# USB_TYPE_C.net
KiCad netlist of a schematic drawn in Altium Designer
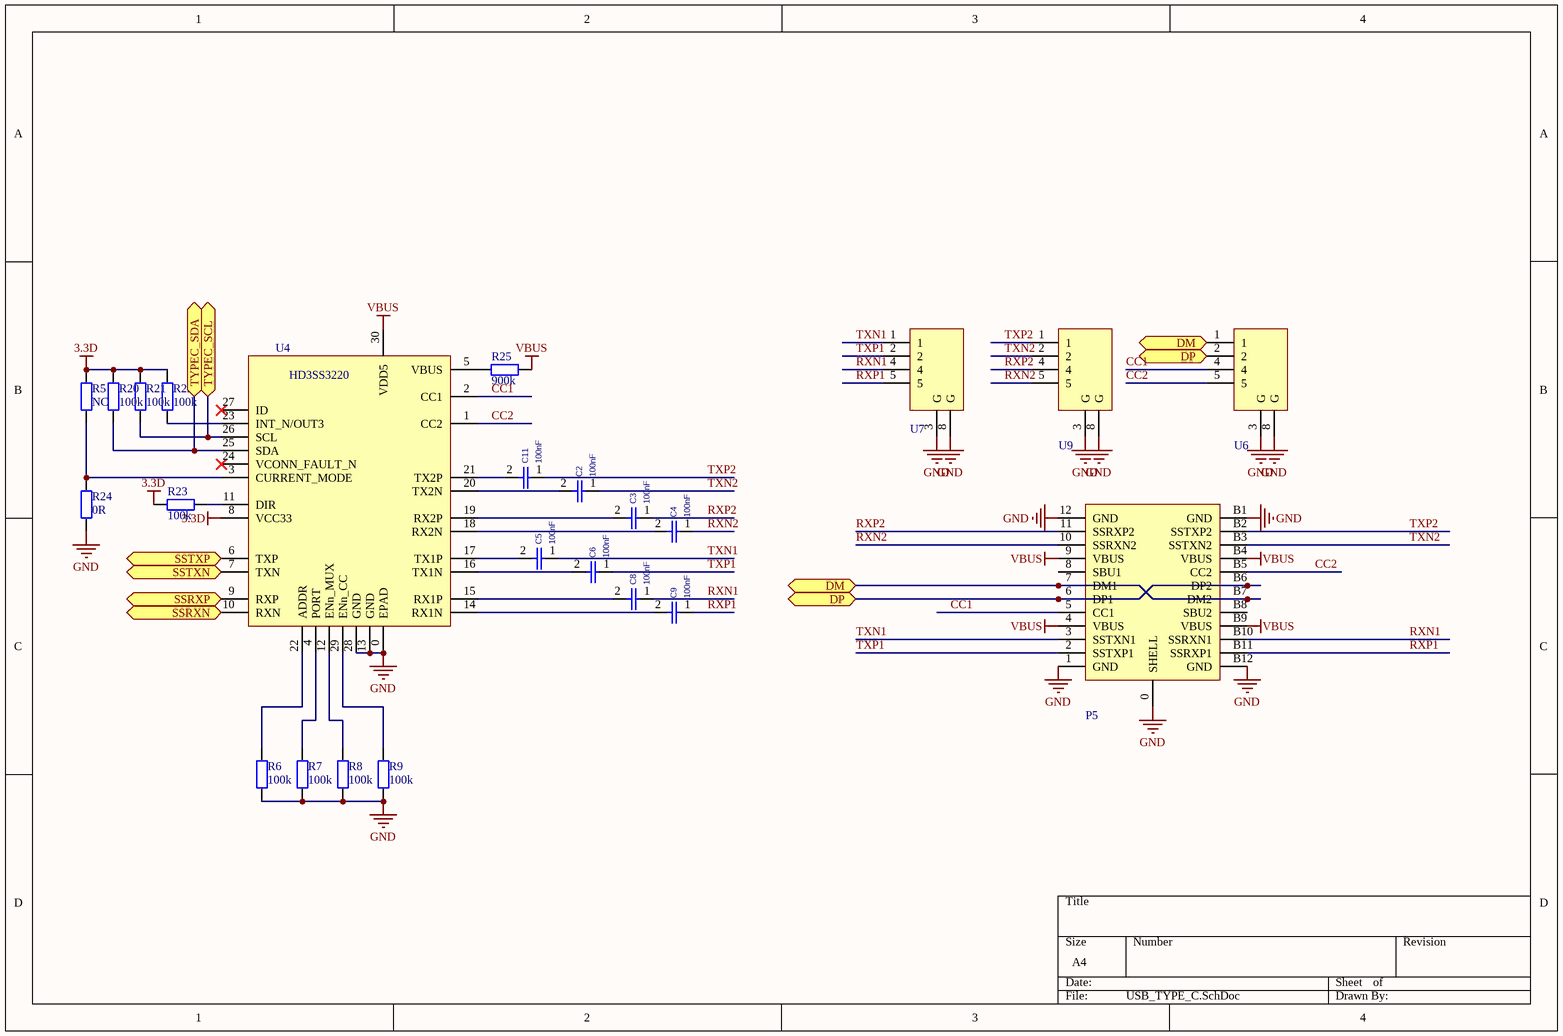
[diagram p0: USB_TYPE_C.SchDoc]

(export (version "E")
  (design (tool "Eeschema 10.0.6"))
  (components
    (comp (ref "C2") (value "100nF") (footprint "0201") (libsource (lib "*") (part "CAP/0402")))
    (comp (ref "C3") (value "100nF") (footprint "0201") (libsource (lib "*") (part "CAP/0402")))
    (comp (ref "C4") (value "100nF") (footprint "0201") (libsource (lib "*") (part "CAP/0402")))
    (comp (ref "C5") (value "100nF") (footprint "0201") (libsource (lib "*") (part "CAP/0402")))
    (comp (ref "C6") (value "100nF") (footprint "0201") (libsource (lib "*") (part "CAP/0402")))
    (comp (ref "C8") (value "100nF") (footprint "0201") (libsource (lib "*") (part "CAP/0402")))
    (comp (ref "C9") (value "100nF") (footprint "0201") (libsource (lib "*") (part "CAP/0402")))
    (comp (ref "C11") (value "100nF") (footprint "0201") (libsource (lib "*") (part "CAP/0402")))
    (comp (ref "P5") (value "TYPEC") (footprint "TYPEC") (libsource (lib "cyusb3014") (part "TYPEC")))
    (comp (ref "R5")
      (value "NC")
      (footprint "0201")
      (description "Resistor")
      (fields (field (name "PUBLISHER") "Altium Limited"))
      (libsource (lib "Miscellaneous Devices") (part "Res2"))
    )
    (comp (ref "R6")
      (value "100k")
      (footprint "0201")
      (description "Resistor")
      (fields (field (name "PUBLISHER") "Altium Limited"))
      (libsource (lib "Miscellaneous Devices") (part "Res2"))
    )
    (comp (ref "R7")
      (value "100k")
      (footprint "0201")
      (description "Resistor")
      (fields (field (name "PUBLISHER") "Altium Limited"))
      (libsource (lib "Miscellaneous Devices") (part "Res2"))
    )
    (comp (ref "R8")
      (value "100k")
      (footprint "0201")
      (description "Resistor")
      (fields (field (name "PUBLISHER") "Altium Limited"))
      (libsource (lib "Miscellaneous Devices") (part "Res2"))
    )
    (comp (ref "R9")
      (value "100k")
      (footprint "0201")
      (description "Resistor")
      (fields (field (name "PUBLISHER") "Altium Limited"))
      (libsource (lib "Miscellaneous Devices") (part "Res2"))
    )
    (comp (ref "R20")
      (value "100k")
      (footprint "0201")
      (description "Resistor")
      (fields (field (name "PUBLISHER") "Altium Limited"))
      (libsource (lib "Miscellaneous Devices") (part "Res2"))
    )
    (comp (ref "R21")
      (value "100k")
      (footprint "0201")
      (description "Resistor")
      (fields (field (name "PUBLISHER") "Altium Limited"))
      (libsource (lib "Miscellaneous Devices") (part "Res2"))
    )
    (comp (ref "R22")
      (value "100k")
      (footprint "0201")
      (description "Resistor")
      (fields (field (name "PUBLISHER") "Altium Limited"))
      (libsource (lib "Miscellaneous Devices") (part "Res2"))
    )
    (comp (ref "R23")
      (value "100k")
      (footprint "0201")
      (description "Resistor")
      (fields (field (name "PUBLISHER") "Altium Limited"))
      (libsource (lib "") (part "Res2_1"))
    )
    (comp (ref "R24")
      (value "0R")
      (footprint "0201")
      (description "Resistor")
      (fields (field (name "PUBLISHER") "Altium Limited"))
      (libsource (lib "Miscellaneous Devices") (part "Res2"))
    )
    (comp (ref "R25")
      (value "900k")
      (footprint "0201")
      (description "Resistor")
      (fields (field (name "PUBLISHER") "Altium Limited"))
      (libsource (lib "") (part "Res2_1"))
    )
    (comp (ref "U4")
      (value "HD3SS3220")
      (footprint "HD3SS3220")
      (libsource (lib "cyusb3014") (part "HD3SS3220"))
    )
    (comp (ref "U6")
      (value "PUSB3FR4")
      (footprint "PUSB3FR4")
      (libsource (lib "cyusb3014") (part "PUSB3FR4"))
    )
    (comp (ref "U7")
      (value "PUSB3FR4")
      (footprint "PUSB3FR4")
      (libsource (lib "cyusb3014") (part "PUSB3FR4"))
    )
    (comp (ref "U9")
      (value "PUSB3FR4")
      (footprint "PUSB3FR4")
      (libsource (lib "cyusb3014") (part "PUSB3FR4"))
    )
  )
  (nets
    (net (code "1") (name "/CC1") (class "Default")
      (node (ref "P5") (pin "5") (pinfunction "CC1_5") (pintype "passive"))
      (node (ref "U4") (pin "2") (pinfunction "CC1_2") (pintype "passive"))
      (node (ref "U6") (pin "4") (pinfunction "4_4") (pintype "passive"))
    )
    (net (code "2") (name "/CC2") (class "Default")
      (node (ref "P5") (pin "B5") (pinfunction "CC2_B5") (pintype "passive"))
      (node (ref "U4") (pin "1") (pinfunction "CC2_1") (pintype "passive"))
      (node (ref "U6") (pin "5") (pinfunction "5_5") (pintype "passive"))
    )
    (net (code "3") (name "/DM") (class "Default")
      (node (ref "P5") (pin "7") (pinfunction "DM1_7") (pintype "passive"))
      (node (ref "P5") (pin "B7") (pinfunction "DM2_B7") (pintype "passive"))
      (node (ref "U6") (pin "1") (pinfunction "1_1") (pintype "passive"))
    )
    (net (code "4") (name "/DP") (class "Default")
      (node (ref "P5") (pin "6") (pinfunction "DP1_6") (pintype "passive"))
      (node (ref "P5") (pin "B6") (pinfunction "DP2_B6") (pintype "passive"))
      (node (ref "U6") (pin "2") (pinfunction "2_2") (pintype "passive"))
    )
    (net (code "5") (name "/RXN1") (class "Default")
      (node (ref "C8") (pin "1") (pinfunction "1_1") (pintype "passive"))
      (node (ref "P5") (pin "B10") (pinfunction "SSRXN1_B10") (pintype "passive"))
      (node (ref "U7") (pin "4") (pinfunction "4_4") (pintype "passive"))
    )
    (net (code "6") (name "/RXN2") (class "Default")
      (node (ref "C4") (pin "1") (pinfunction "1_1") (pintype "passive"))
      (node (ref "P5") (pin "10") (pinfunction "SSRXN2_10") (pintype "passive"))
      (node (ref "U9") (pin "5") (pinfunction "5_5") (pintype "passive"))
    )
    (net (code "7") (name "/RXP1") (class "Default")
      (node (ref "C9") (pin "1") (pinfunction "1_1") (pintype "passive"))
      (node (ref "P5") (pin "B11") (pinfunction "SSRXP1_B11") (pintype "passive"))
      (node (ref "U7") (pin "5") (pinfunction "5_5") (pintype "passive"))
    )
    (net (code "8") (name "/RXP2") (class "Default")
      (node (ref "C3") (pin "1") (pinfunction "1_1") (pintype "passive"))
      (node (ref "P5") (pin "11") (pinfunction "SSRXP2_11") (pintype "passive"))
      (node (ref "U9") (pin "4") (pinfunction "4_4") (pintype "passive"))
    )
    (net (code "9") (name "/SSRXN") (class "Default")
      (node (ref "U4") (pin "10") (pinfunction "RXN_10") (pintype "passive"))
    )
    (net (code "10") (name "/SSRXP") (class "Default")
      (node (ref "U4") (pin "9") (pinfunction "RXP_9") (pintype "passive"))
    )
    (net (code "11") (name "/SSTXN") (class "Default")
      (node (ref "U4") (pin "7") (pinfunction "TXN_7") (pintype "passive"))
    )
    (net (code "12") (name "/SSTXP") (class "Default")
      (node (ref "U4") (pin "6") (pinfunction "TXP_6") (pintype "passive"))
    )
    (net (code "13") (name "/TXN1") (class "Default")
      (node (ref "C5") (pin "1") (pinfunction "1_1") (pintype "passive"))
      (node (ref "P5") (pin "3") (pinfunction "SSTXN1_3") (pintype "passive"))
      (node (ref "U7") (pin "1") (pinfunction "1_1") (pintype "passive"))
    )
    (net (code "14") (name "/TXN2") (class "Default")
      (node (ref "C2") (pin "1") (pinfunction "1_1") (pintype "passive"))
      (node (ref "P5") (pin "B3") (pinfunction "SSTXN2_B3") (pintype "passive"))
      (node (ref "U9") (pin "2") (pinfunction "2_2") (pintype "passive"))
    )
    (net (code "15") (name "/TXP1") (class "Default")
      (node (ref "C6") (pin "1") (pinfunction "1_1") (pintype "passive"))
      (node (ref "P5") (pin "2") (pinfunction "SSTXP1_2") (pintype "passive"))
      (node (ref "U7") (pin "2") (pinfunction "2_2") (pintype "passive"))
    )
    (net (code "16") (name "/TXP2") (class "Default")
      (node (ref "C11") (pin "1") (pinfunction "1_1") (pintype "passive"))
      (node (ref "P5") (pin "B2") (pinfunction "SSTXP2_B2") (pintype "passive"))
      (node (ref "U9") (pin "1") (pinfunction "1_1") (pintype "passive"))
    )
    (net (code "17") (name "/TYPEC_SCL") (class "Default")
      (node (ref "R21") (pin "1") (pinfunction "1_1") (pintype "passive"))
      (node (ref "U4") (pin "26") (pinfunction "SCL_26") (pintype "passive"))
    )
    (net (code "18") (name "/TYPEC_SDA") (class "Default")
      (node (ref "R20") (pin "1") (pinfunction "1_1") (pintype "passive"))
      (node (ref "U4") (pin "25") (pinfunction "SDA_25") (pintype "passive"))
    )
    (net (code "19") (name "3.3D") (class "Default")
      (node (ref "R20") (pin "2") (pinfunction "2_2") (pintype "passive"))
      (node (ref "R21") (pin "2") (pinfunction "2_2") (pintype "passive"))
      (node (ref "R22") (pin "2") (pinfunction "2_2") (pintype "passive"))
      (node (ref "R23") (pin "1") (pinfunction "1_1") (pintype "passive"))
      (node (ref "R5") (pin "2") (pinfunction "2_2") (pintype "passive"))
      (node (ref "U4") (pin "8") (pinfunction "VCC33_8") (pintype "passive"))
    )
    (net (code "20") (name "GND") (class "Default")
      (node (ref "P5") (pin "0") (pinfunction "SHELL_0") (pintype "passive"))
      (node (ref "P5") (pin "1") (pinfunction "GND_1") (pintype "passive"))
      (node (ref "P5") (pin "12") (pinfunction "GND_12") (pintype "passive"))
      (node (ref "P5") (pin "B1") (pinfunction "GND_B1") (pintype "passive"))
      (node (ref "P5") (pin "B12") (pinfunction "GND_B12") (pintype "passive"))
      (node (ref "R24") (pin "1") (pinfunction "1_1") (pintype "passive"))
      (node (ref "R6") (pin "1") (pinfunction "1_1") (pintype "passive"))
      (node (ref "R7") (pin "1") (pinfunction "1_1") (pintype "passive"))
      (node (ref "R8") (pin "1") (pinfunction "1_1") (pintype "passive"))
      (node (ref "R9") (pin "1") (pinfunction "1_1") (pintype "passive"))
      (node (ref "U4") (pin "0") (pinfunction "EPAD_0") (pintype "passive"))
      (node (ref "U4") (pin "13") (pinfunction "GND_13") (pintype "passive"))
      (node (ref "U4") (pin "28") (pinfunction "GND_28") (pintype "passive"))
      (node (ref "U6") (pin "3") (pinfunction "G_3") (pintype "passive"))
      (node (ref "U6") (pin "8") (pinfunction "G_8") (pintype "passive"))
      (node (ref "U7") (pin "3") (pinfunction "G_3") (pintype "passive"))
      (node (ref "U7") (pin "8") (pinfunction "G_8") (pintype "passive"))
      (node (ref "U9") (pin "3") (pinfunction "G_3") (pintype "passive"))
      (node (ref "U9") (pin "8") (pinfunction "G_8") (pintype "passive"))
    )
    (net (code "21") (name "Net-(U4-ADDR)") (class "Default")
      (node (ref "R6") (pin "2") (pinfunction "2_2") (pintype "passive"))
      (node (ref "U4") (pin "22") (pinfunction "ADDR_22") (pintype "passive"))
    )
    (net (code "22") (name "Net-(U4-CURRENT_MODE)") (class "Default")
      (node (ref "R24") (pin "2") (pinfunction "2_2") (pintype "passive"))
      (node (ref "R5") (pin "1") (pinfunction "1_1") (pintype "passive"))
      (node (ref "U4") (pin "3") (pinfunction "CURRENT_MODE_3") (pintype "passive"))
    )
    (net (code "23") (name "Net-(U4-DIR)") (class "Default")
      (node (ref "R23") (pin "2") (pinfunction "2_2") (pintype "passive"))
      (node (ref "U4") (pin "11") (pinfunction "DIR_11") (pintype "passive"))
    )
    (net (code "24") (name "Net-(U4-ENn_CC)") (class "Default")
      (node (ref "R9") (pin "2") (pinfunction "2_2") (pintype "passive"))
      (node (ref "U4") (pin "29") (pinfunction "ENn_CC_29") (pintype "passive"))
    )
    (net (code "25") (name "Net-(U4-ENn_MUX)") (class "Default")
      (node (ref "R8") (pin "2") (pinfunction "2_2") (pintype "passive"))
      (node (ref "U4") (pin "12") (pinfunction "ENn_MUX_12") (pintype "passive"))
    )
    (net (code "26") (name "Net-(U4-INT_N{slash}OUT3)") (class "Default")
      (node (ref "R22") (pin "1") (pinfunction "1_1") (pintype "passive"))
      (node (ref "U4") (pin "23") (pinfunction "INT_N/OUT3_23") (pintype "passive"))
    )
    (net (code "27") (name "Net-(U4-PORT)") (class "Default")
      (node (ref "R7") (pin "2") (pinfunction "2_2") (pintype "passive"))
      (node (ref "U4") (pin "4") (pinfunction "PORT_4") (pintype "passive"))
    )
    (net (code "28") (name "Net-(U4-RX1N)") (class "Default")
      (node (ref "C9") (pin "2") (pinfunction "2_2") (pintype "passive"))
      (node (ref "U4") (pin "14") (pinfunction "RX1N_14") (pintype "passive"))
    )
    (net (code "29") (name "Net-(U4-RX1P)") (class "Default")
      (node (ref "C8") (pin "2") (pinfunction "2_2") (pintype "passive"))
      (node (ref "U4") (pin "15") (pinfunction "RX1P_15") (pintype "passive"))
    )
    (net (code "30") (name "Net-(U4-RX2N)") (class "Default")
      (node (ref "C4") (pin "2") (pinfunction "2_2") (pintype "passive"))
      (node (ref "U4") (pin "18") (pinfunction "RX2N_18") (pintype "passive"))
    )
    (net (code "31") (name "Net-(U4-RX2P)") (class "Default")
      (node (ref "C3") (pin "2") (pinfunction "2_2") (pintype "passive"))
      (node (ref "U4") (pin "19") (pinfunction "RX2P_19") (pintype "passive"))
    )
    (net (code "32") (name "Net-(U4-TX1N)") (class "Default")
      (node (ref "C6") (pin "2") (pinfunction "2_2") (pintype "passive"))
      (node (ref "U4") (pin "16") (pinfunction "TX1N_16") (pintype "passive"))
    )
    (net (code "33") (name "Net-(U4-TX1P)") (class "Default")
      (node (ref "C5") (pin "2") (pinfunction "2_2") (pintype "passive"))
      (node (ref "U4") (pin "17") (pinfunction "TX1P_17") (pintype "passive"))
    )
    (net (code "34") (name "Net-(U4-TX2N)") (class "Default")
      (node (ref "C2") (pin "2") (pinfunction "2_2") (pintype "passive"))
      (node (ref "U4") (pin "20") (pinfunction "TX2N_20") (pintype "passive"))
    )
    (net (code "35") (name "Net-(U4-TX2P)") (class "Default")
      (node (ref "C11") (pin "2") (pinfunction "2_2") (pintype "passive"))
      (node (ref "U4") (pin "21") (pinfunction "TX2P_21") (pintype "passive"))
    )
    (net (code "36") (name "Net-(U4-VBUS)") (class "Default")
      (node (ref "R25") (pin "1") (pinfunction "1_1") (pintype "passive"))
      (node (ref "U4") (pin "5") (pinfunction "VBUS_5") (pintype "passive"))
    )
    (net (code "37") (name "VBUS") (class "Default")
      (node (ref "P5") (pin "4") (pinfunction "VBUS_4") (pintype "passive"))
      (node (ref "P5") (pin "9") (pinfunction "VBUS_9") (pintype "passive"))
      (node (ref "P5") (pin "B4") (pinfunction "VBUS_B4") (pintype "passive"))
      (node (ref "P5") (pin "B9") (pinfunction "VBUS_B9") (pintype "passive"))
      (node (ref "R25") (pin "2") (pinfunction "2_2") (pintype "passive"))
      (node (ref "U4") (pin "30") (pinfunction "VDD5_30") (pintype "passive"))
    )
    (net (code "38") (name "unconnected-(P5-SBU1-Pad8)") (class "Default")
      (node (ref "P5") (pin "8") (pinfunction "SBU1_8") (pintype "passive"))
    )
    (net (code "39") (name "unconnected-(P5-SBU2-PadB8)") (class "Default")
      (node (ref "P5") (pin "B8") (pinfunction "SBU2_B8") (pintype "passive"))
    )
    (net (code "40") (name "unconnected-(U4-ID-Pad27)") (class "Default")
      (node (ref "U4") (pin "27") (pinfunction "ID_27") (pintype "passive+no_connect"))
    )
    (net (code "41") (name "unconnected-(U4-VCONN_FAULT_N-Pad24)") (class "Default")
      (node (ref "U4") (pin "24") (pinfunction "VCONN_FAULT_N_24") (pintype "passive+no_connect"))
    )
  )
)
